# galvanika-board-1_0.net
KiCad netlist of a schematic drawn in EAGLE
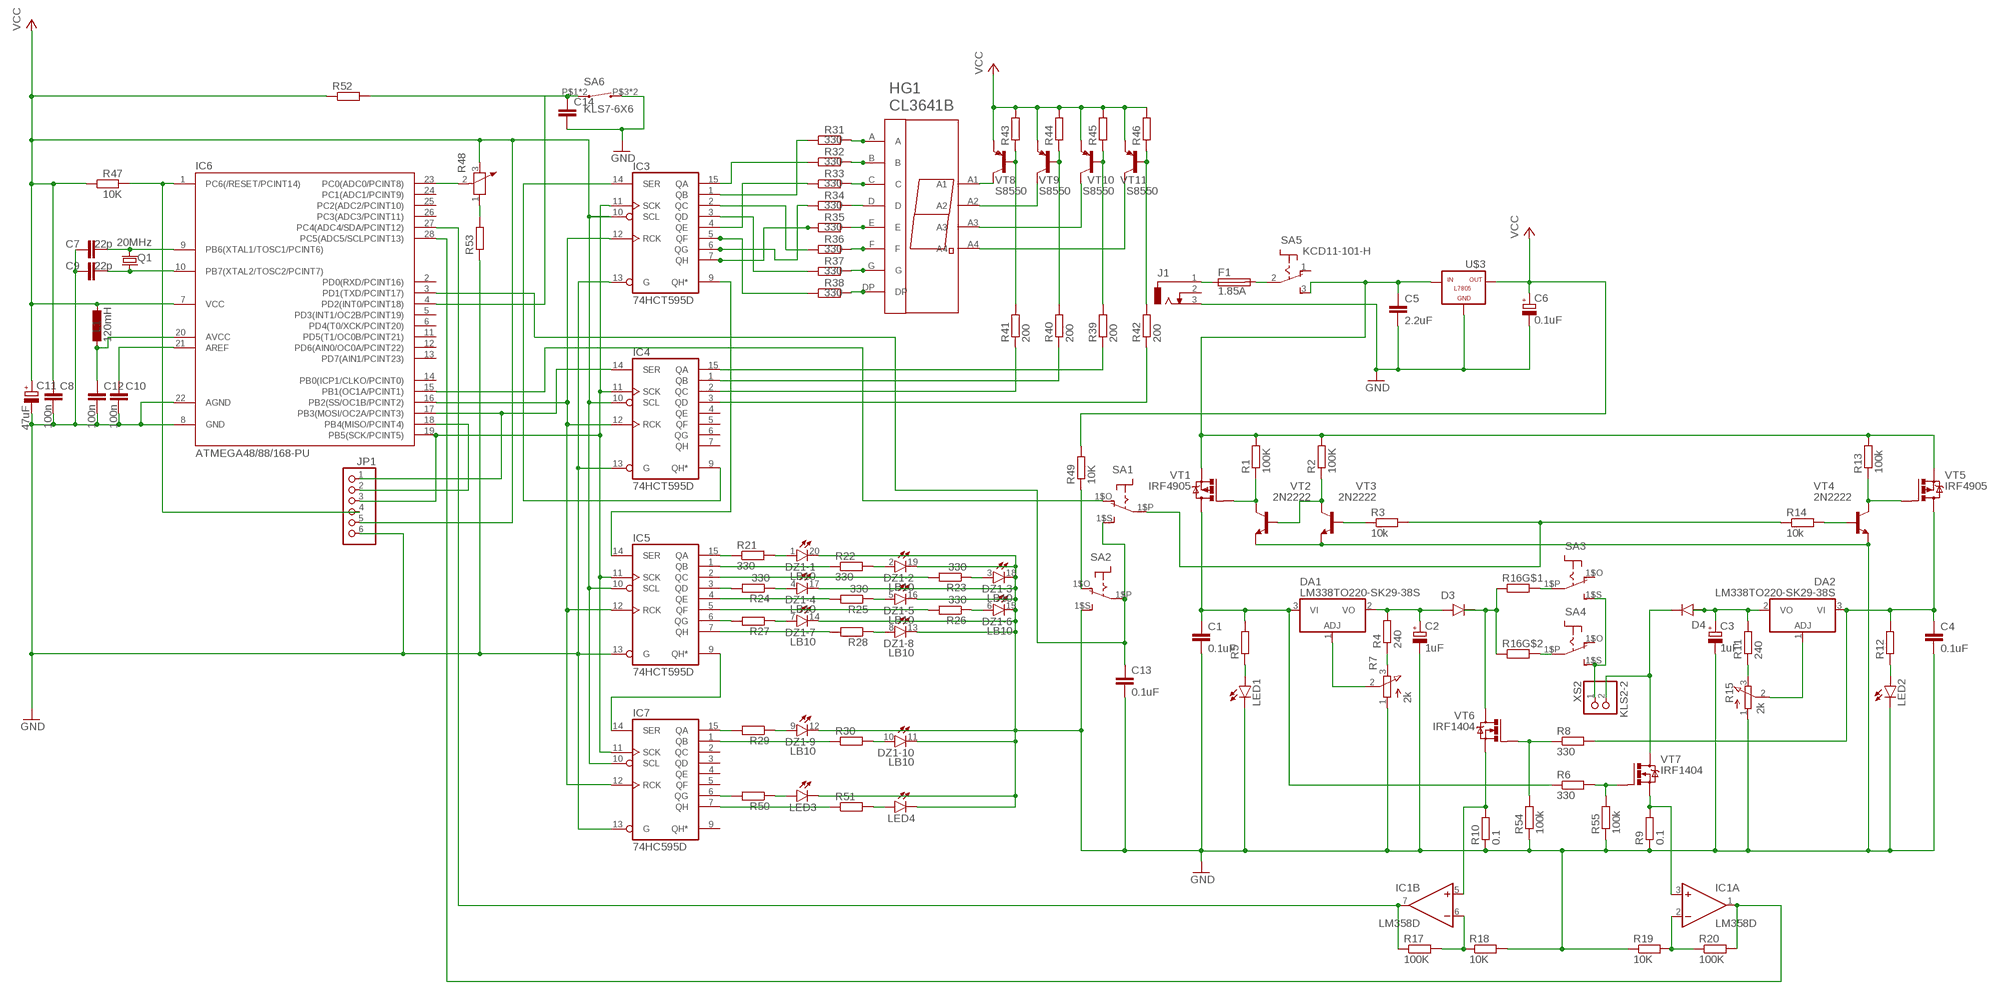
[diagram p0: schematic, sheet 1]

(export (version "E")
  (design (tool "Eeschema 10.0.6"))
  (components
    (comp (ref "C1")
      (value "0.1uF")
      (footprint "eagle-import:C1206")
      (libsource (lib "eagle-import") (part "rcl_334_C-EUC1206"))
    )
    (comp (ref "C2")
      (value "1uF")
      (footprint "eagle-import:E5-4")
      (libsource (lib "eagle-import") (part "CPOL-EUE5-4"))
    )
    (comp (ref "C3")
      (value "1uF")
      (footprint "eagle-import:E5-4")
      (libsource (lib "eagle-import") (part "CPOL-EUE5-4"))
    )
    (comp (ref "C4")
      (value "0.1uF")
      (footprint "eagle-import:C1206")
      (libsource (lib "eagle-import") (part "rcl_334_C-EUC1206"))
    )
    (comp (ref "C5")
      (value "2.2uF")
      (footprint "eagle-import:C025-025X050")
      (libsource (lib "eagle-import") (part "C-EU025-025X050"))
    )
    (comp (ref "C6")
      (value "0.1uF")
      (footprint "eagle-import:E2,5-5")
      (libsource (lib "eagle-import") (part "rcl_334_CPOL-EUE2.5-5"))
    )
    (comp (ref "C7")
      (value "22p")
      (footprint "eagle-import:C025-025X050")
      (libsource (lib "eagle-import") (part "rcl_334_C-EU025-025X050"))
    )
    (comp (ref "C8")
      (value "100n")
      (footprint "eagle-import:C025-025X050")
      (libsource (lib "eagle-import") (part "rcl_334_C-EU025-025X050"))
    )
    (comp (ref "C9")
      (value "22p")
      (footprint "eagle-import:C025-025X050")
      (libsource (lib "eagle-import") (part "rcl_334_C-EU025-025X050"))
    )
    (comp (ref "C10")
      (value "100n")
      (footprint "eagle-import:C025-025X050")
      (libsource (lib "eagle-import") (part "rcl_334_C-EU025-025X050"))
    )
    (comp (ref "C11")
      (value "47uF")
      (footprint "eagle-import:E2-4")
      (libsource (lib "eagle-import") (part "rcl_334_CPOL-EUE2-4"))
    )
    (comp (ref "C12")
      (value "100n")
      (footprint "eagle-import:C025-025X050")
      (libsource (lib "eagle-import") (part "rcl_334_C-EU025-025X050"))
    )
    (comp (ref "C13")
      (value "0.1uF")
      (footprint "eagle-import:C1206")
      (libsource (lib "eagle-import") (part "C-EUC1206"))
    )
    (comp (ref "C14")
      (value "C-EUC1206")
      (footprint "eagle-import:C1206")
      (libsource (lib "eagle-import") (part "C-EUC1206"))
    )
    (comp (ref "D3")
      (value "1N4001")
      (footprint "eagle-import:DO41-10")
      (libsource (lib "eagle-import") (part "1N4001"))
    )
    (comp (ref "D4")
      (value "1N4001")
      (footprint "eagle-import:DO41-10")
      (libsource (lib "eagle-import") (part "1N4001"))
    )
    (comp (ref "DA1")
      (value "LM338TO220-SK29-38S")
      (footprint "eagle-import:TO220-SK29-38S")
      (libsource (lib "eagle-import") (part "LM338TO220-SK29-38S"))
    )
    (comp (ref "DA2")
      (value "LM338TO220-SK29-38S")
      (footprint "eagle-import:TO220-SK29-38S")
      (libsource (lib "eagle-import") (part "LM338TO220-SK29-38S"))
    )
    (comp (ref "DZ1")
      (value "LB10")
      (footprint "eagle-import:LB10")
      (libsource (lib "eagle-import") (part "LB10"))
    )
    (comp (ref "F1")
      (value "1.85A")
      (footprint "eagle-import:MF-R")
      (libsource (lib "eagle-import") (part "MF-R"))
    )
    (comp (ref "HG1")
      (value "CL3641B")
      (footprint "eagle-import:CL3641B")
      (libsource (lib "eagle-import") (part "CL3641B"))
    )
    (comp (ref "IC1")
      (value "LM358D")
      (footprint "eagle-import:SO08")
      (libsource (lib "eagle-import") (part "LM358D"))
    )
    (comp (ref "IC3")
      (value "74HCT595D")
      (footprint "eagle-import:SO16")
      (libsource (lib "eagle-import") (part "74595DHCT"))
    )
    (comp (ref "IC4")
      (value "74HCT595D")
      (footprint "eagle-import:SO16")
      (libsource (lib "eagle-import") (part "74595DHCT"))
    )
    (comp (ref "IC5")
      (value "74HCT595D")
      (footprint "eagle-import:SO16")
      (libsource (lib "eagle-import") (part "74595DHCT"))
    )
    (comp (ref "IC6")
      (value "ATMEGA48/88/168-PU")
      (footprint "eagle-import:DIL28-3")
      (libsource (lib "eagle-import") (part "ATMEGA48/88/168-PU"))
    )
    (comp (ref "IC7")
      (value "74HC595D")
      (footprint "eagle-import:SO16")
      (libsource (lib "eagle-import") (part "74595DHC"))
    )
    (comp (ref "J1")
      (value "DCJ0303")
      (footprint "eagle-import:DCJ0303")
      (libsource (lib "eagle-import") (part "DCJ0303"))
    )
    (comp (ref "JP1")
      (value "PINHD-1X6")
      (footprint "eagle-import:1X06")
      (libsource (lib "eagle-import") (part "PINHD-1X6"))
    )
    (comp (ref "L1")
      (value "120mH")
      (footprint "eagle-import:0207_10")
      (libsource (lib "eagle-import") (part "L-EU0207/10"))
    )
    (comp (ref "LED1")
      (value "LED3MM")
      (footprint "eagle-import:LED3MM")
      (libsource (lib "eagle-import") (part "LED3MM"))
    )
    (comp (ref "LED2")
      (value "LED3MM")
      (footprint "eagle-import:LED3MM")
      (libsource (lib "eagle-import") (part "LED3MM"))
    )
    (comp (ref "LED3")
      (value "LED3MM")
      (footprint "eagle-import:LED3MM")
      (libsource (lib "eagle-import") (part "LED3MM"))
    )
    (comp (ref "LED4")
      (value "LED3MM")
      (footprint "eagle-import:LED3MM")
      (libsource (lib "eagle-import") (part "LED3MM"))
    )
    (comp (ref "Q1")
      (value "20MHz")
      (footprint "eagle-import:HC49_S")
      (libsource (lib "eagle-import") (part "CRYSTALHC49S"))
    )
    (comp (ref "R1")
      (value "100K")
      (footprint "eagle-import:0207_10")
      (libsource (lib "eagle-import") (part "rcl_334_R-EU_0207/10"))
    )
    (comp (ref "R2")
      (value "100K")
      (footprint "eagle-import:0207_10")
      (libsource (lib "eagle-import") (part "rcl_334_R-EU_0207/10"))
    )
    (comp (ref "R3")
      (value "10k")
      (footprint "eagle-import:0207_10")
      (libsource (lib "eagle-import") (part "rcl_334_R-EU_0207/10"))
    )
    (comp (ref "R4")
      (value "240")
      (footprint "eagle-import:0207_10")
      (libsource (lib "eagle-import") (part "R-EU_0207/10"))
    )
    (comp (ref "R5")
      (value "R-EU_0207/10")
      (footprint "eagle-import:0207_10")
      (libsource (lib "eagle-import") (part "R-EU_0207/10"))
    )
    (comp (ref "R6")
      (value "330")
      (footprint "eagle-import:0207_10")
      (libsource (lib "eagle-import") (part "rcl_334_R-EU_0207/10"))
    )
    (comp (ref "R7")
      (value "2k")
      (footprint "eagle-import:3RP_1610N")
      (libsource (lib "eagle-import") (part "3RP/1610N"))
    )
    (comp (ref "R8")
      (value "330")
      (footprint "eagle-import:0207_10")
      (libsource (lib "eagle-import") (part "rcl_334_R-EU_0207/10"))
    )
    (comp (ref "R9")
      (value "0.1")
      (footprint "eagle-import:0411_12")
      (libsource (lib "eagle-import") (part "rcl_334_R-EU_0411/12"))
    )
    (comp (ref "R10")
      (value "0.1")
      (footprint "eagle-import:0411_12")
      (libsource (lib "eagle-import") (part "rcl_334_R-EU_0411/12"))
    )
    (comp (ref "R11")
      (value "240")
      (footprint "eagle-import:0207_10")
      (libsource (lib "eagle-import") (part "rcl_334_R-EU_0207/10"))
    )
    (comp (ref "R12")
      (value "R-EU_0207/10")
      (footprint "eagle-import:0207_10")
      (libsource (lib "eagle-import") (part "R-EU_0207/10"))
    )
    (comp (ref "R13")
      (value "100k")
      (footprint "eagle-import:0207_10")
      (libsource (lib "eagle-import") (part "rcl_334_R-EU_0207/10"))
    )
    (comp (ref "R14")
      (value "10k")
      (footprint "eagle-import:0207_10")
      (libsource (lib "eagle-import") (part "rcl_334_R-EU_0207/10"))
    )
    (comp (ref "R15")
      (value "2k")
      (footprint "eagle-import:3RP_1610N")
      (libsource (lib "eagle-import") (part "3RP/1610N"))
    )
    (comp (ref "R16")
      (value "SQP-5W-2")
      (footprint "eagle-import:SQP-5W-2")
      (libsource (lib "eagle-import") (part "SQP-5W-2"))
    )
    (comp (ref "R17")
      (value "100K")
      (footprint "eagle-import:R1206")
      (libsource (lib "eagle-import") (part "rcl_334_R-EU_R1206"))
    )
    (comp (ref "R18")
      (value "10K")
      (footprint "eagle-import:R1206")
      (libsource (lib "eagle-import") (part "rcl_334_R-EU_R1206"))
    )
    (comp (ref "R19")
      (value "10K")
      (footprint "eagle-import:R1206")
      (libsource (lib "eagle-import") (part "rcl_334_R-EU_R1206"))
    )
    (comp (ref "R20")
      (value "100K")
      (footprint "eagle-import:R1206")
      (libsource (lib "eagle-import") (part "rcl_334_R-EU_R1206"))
    )
    (comp (ref "R21")
      (value "330")
      (footprint "eagle-import:R1206")
      (libsource (lib "eagle-import") (part "rcl_334_R-EU_R1206"))
    )
    (comp (ref "R22")
      (value "330")
      (footprint "eagle-import:R1206")
      (libsource (lib "eagle-import") (part "rcl_334_R-EU_R1206"))
    )
    (comp (ref "R23")
      (value "330")
      (footprint "eagle-import:R1206")
      (libsource (lib "eagle-import") (part "rcl_334_R-EU_R1206"))
    )
    (comp (ref "R24")
      (value "330")
      (footprint "eagle-import:R1206")
      (libsource (lib "eagle-import") (part "rcl_334_R-EU_R1206"))
    )
    (comp (ref "R25")
      (value "330")
      (footprint "eagle-import:R1206")
      (libsource (lib "eagle-import") (part "rcl_334_R-EU_R1206"))
    )
    (comp (ref "R26")
      (value "330")
      (footprint "eagle-import:R1206")
      (libsource (lib "eagle-import") (part "rcl_334_R-EU_R1206"))
    )
    (comp (ref "R27")
      (value "R-EU_R1206")
      (footprint "eagle-import:R1206")
      (libsource (lib "eagle-import") (part "rcl_334_R-EU_R1206"))
    )
    (comp (ref "R28")
      (value "R-EU_R1206")
      (footprint "eagle-import:R1206")
      (libsource (lib "eagle-import") (part "rcl_334_R-EU_R1206"))
    )
    (comp (ref "R29")
      (value "R-EU_R1206")
      (footprint "eagle-import:R1206")
      (libsource (lib "eagle-import") (part "rcl_334_R-EU_R1206"))
    )
    (comp (ref "R30")
      (value "R-EU_R1206")
      (footprint "eagle-import:R1206")
      (libsource (lib "eagle-import") (part "rcl_334_R-EU_R1206"))
    )
    (comp (ref "R31")
      (value "330")
      (footprint "eagle-import:R1206")
      (libsource (lib "eagle-import") (part "rcl_334_R-EU_R1206"))
    )
    (comp (ref "R32")
      (value "330")
      (footprint "eagle-import:R1206")
      (libsource (lib "eagle-import") (part "rcl_334_R-EU_R1206"))
    )
    (comp (ref "R33")
      (value "330")
      (footprint "eagle-import:R1206")
      (libsource (lib "eagle-import") (part "rcl_334_R-EU_R1206"))
    )
    (comp (ref "R34")
      (value "330")
      (footprint "eagle-import:R1206")
      (libsource (lib "eagle-import") (part "rcl_334_R-EU_R1206"))
    )
    (comp (ref "R35")
      (value "330")
      (footprint "eagle-import:R1206")
      (libsource (lib "eagle-import") (part "rcl_334_R-EU_R1206"))
    )
    (comp (ref "R36")
      (value "330")
      (footprint "eagle-import:R1206")
      (libsource (lib "eagle-import") (part "rcl_334_R-EU_R1206"))
    )
    (comp (ref "R37")
      (value "330")
      (footprint "eagle-import:R1206")
      (libsource (lib "eagle-import") (part "rcl_334_R-EU_R1206"))
    )
    (comp (ref "R38")
      (value "330")
      (footprint "eagle-import:R1206")
      (libsource (lib "eagle-import") (part "rcl_334_R-EU_R1206"))
    )
    (comp (ref "R39")
      (value "200")
      (footprint "eagle-import:R1206")
      (libsource (lib "eagle-import") (part "rcl_334_R-EU_R1206"))
    )
    (comp (ref "R40")
      (value "200")
      (footprint "eagle-import:R1206")
      (libsource (lib "eagle-import") (part "rcl_334_R-EU_R1206"))
    )
    (comp (ref "R41")
      (value "200")
      (footprint "eagle-import:R1206")
      (libsource (lib "eagle-import") (part "rcl_334_R-EU_R1206"))
    )
    (comp (ref "R42")
      (value "200")
      (footprint "eagle-import:R1206")
      (libsource (lib "eagle-import") (part "rcl_334_R-EU_R1206"))
    )
    (comp (ref "R43")
      (value "R-EU_R1206")
      (footprint "eagle-import:R1206")
      (libsource (lib "eagle-import") (part "R-EU_R1206"))
    )
    (comp (ref "R44")
      (value "R-EU_R1206")
      (footprint "eagle-import:R1206")
      (libsource (lib "eagle-import") (part "R-EU_R1206"))
    )
    (comp (ref "R45")
      (value "R-EU_R1206")
      (footprint "eagle-import:R1206")
      (libsource (lib "eagle-import") (part "R-EU_R1206"))
    )
    (comp (ref "R46")
      (value "R-EU_R1206")
      (footprint "eagle-import:R1206")
      (libsource (lib "eagle-import") (part "R-EU_R1206"))
    )
    (comp (ref "R47")
      (value "10K")
      (footprint "eagle-import:0207_10")
      (libsource (lib "eagle-import") (part "R-EU_0207/10"))
    )
    (comp (ref "R48")
      (value "R0904N")
      (footprint "eagle-import:R0904N")
      (libsource (lib "eagle-import") (part "R0904N"))
    )
    (comp (ref "R49")
      (value "10K")
      (footprint "eagle-import:0207_10")
      (libsource (lib "eagle-import") (part "R-EU_0207/10"))
    )
    (comp (ref "R50")
      (value "R-EU_R1206")
      (footprint "eagle-import:R1206")
      (libsource (lib "eagle-import") (part "rcl_334_R-EU_R1206"))
    )
    (comp (ref "R51")
      (value "R-EU_R1206")
      (footprint "eagle-import:R1206")
      (libsource (lib "eagle-import") (part "rcl_334_R-EU_R1206"))
    )
    (comp (ref "R52")
      (value "R-EU_R1206")
      (footprint "eagle-import:R1206")
      (libsource (lib "eagle-import") (part "R-EU_R1206"))
    )
    (comp (ref "R53")
      (value "R-EU_R1206")
      (footprint "eagle-import:R1206")
      (libsource (lib "eagle-import") (part "R-EU_R1206"))
    )
    (comp (ref "R54")
      (value "100k")
      (footprint "eagle-import:R1206")
      (libsource (lib "eagle-import") (part "R-EU_R1206"))
    )
    (comp (ref "R55")
      (value "100k")
      (footprint "eagle-import:R1206")
      (libsource (lib "eagle-import") (part "R-EU_R1206"))
    )
    (comp (ref "SA1")
      (value "SS12D00DIP")
      (footprint "eagle-import:SS12D00")
      (libsource (lib "eagle-import") (part "SS12D00DIP"))
    )
    (comp (ref "SA2")
      (value "SS12D00DIP")
      (footprint "eagle-import:SS12D00")
      (libsource (lib "eagle-import") (part "SS12D00DIP"))
    )
    (comp (ref "SA3")
      (value "SS12D00DIP")
      (footprint "eagle-import:SS12D00")
      (libsource (lib "eagle-import") (part "SS12D00DIP"))
    )
    (comp (ref "SA4")
      (value "SS12D00DIP")
      (footprint "eagle-import:SS12D00")
      (libsource (lib "eagle-import") (part "SS12D00DIP"))
    )
    (comp (ref "SA5")
      (value "KCD11-101-H")
      (footprint "eagle-import:KCD11-101-H")
      (libsource (lib "eagle-import") (part "KCD11-101-H"))
    )
    (comp (ref "SA6")
      (value "KLS7-6X6")
      (footprint "eagle-import:KLS7-6X6")
      (libsource (lib "eagle-import") (part "KLS7-6X6"))
    )
    (comp (ref "U$3")
      (value "L7805")
      (footprint "eagle-import:TO220-SK29-38S")
      (libsource (lib "eagle-import") (part "L7805"))
    )
    (comp (ref "VT1")
      (value "IRF4905")
      (footprint "eagle-import:TO220-V")
      (libsource (lib "eagle-import") (part "IRF4905"))
    )
    (comp (ref "VT2")
      (value "2N2222")
      (footprint "eagle-import:TO92")
      (libsource (lib "eagle-import") (part "2N2222"))
    )
    (comp (ref "VT3")
      (value "2N2222")
      (footprint "eagle-import:TO92")
      (libsource (lib "eagle-import") (part "2N2222"))
    )
    (comp (ref "VT4")
      (value "2N2222")
      (footprint "eagle-import:TO92")
      (libsource (lib "eagle-import") (part "2N2222"))
    )
    (comp (ref "VT5")
      (value "IRF4905")
      (footprint "eagle-import:TO220-V")
      (libsource (lib "eagle-import") (part "IRF4905"))
    )
    (comp (ref "VT6")
      (value "IRF1404")
      (footprint "eagle-import:TO220-V")
      (libsource (lib "eagle-import") (part "IRF1404"))
    )
    (comp (ref "VT7")
      (value "IRF1404")
      (footprint "eagle-import:TO220-V")
      (libsource (lib "eagle-import") (part "IRF1404"))
    )
    (comp (ref "VT8")
      (value "S8550")
      (footprint "eagle-import:TO92")
      (libsource (lib "eagle-import") (part "S8550"))
    )
    (comp (ref "VT9")
      (value "S8550")
      (footprint "eagle-import:TO92")
      (libsource (lib "eagle-import") (part "S8550"))
    )
    (comp (ref "VT10")
      (value "S8550")
      (footprint "eagle-import:TO92")
      (libsource (lib "eagle-import") (part "S8550"))
    )
    (comp (ref "VT11")
      (value "S8550")
      (footprint "eagle-import:TO92")
      (libsource (lib "eagle-import") (part "S8550"))
    )
    (comp (ref "XS2")
      (value "KLS2-2")
      (footprint "eagle-import:KLS2-2")
      (libsource (lib "eagle-import") (part "KLS2-2"))
    )
  )
  (nets
    (net (code "1") (name "GND") (class "Default")
      (node (ref "C1") (pin "2") (pinfunction "2_2") (pintype "passive"))
      (node (ref "C10") (pin "2") (pinfunction "2_2") (pintype "passive"))
      (node (ref "C11") (pin "-") (pinfunction "-_-") (pintype "passive"))
      (node (ref "C12") (pin "2") (pinfunction "2_2") (pintype "passive"))
      (node (ref "C13") (pin "2") (pinfunction "2_2") (pintype "passive"))
      (node (ref "C14") (pin "2") (pinfunction "2_2") (pintype "passive"))
      (node (ref "C2") (pin "-") (pinfunction "-_-") (pintype "passive"))
      (node (ref "C3") (pin "-") (pinfunction "-_-") (pintype "passive"))
      (node (ref "C4") (pin "2") (pinfunction "2_2") (pintype "passive"))
      (node (ref "C5") (pin "2") (pinfunction "2_2") (pintype "passive"))
      (node (ref "C6") (pin "-") (pinfunction "-_-") (pintype "passive"))
      (node (ref "C7") (pin "1") (pinfunction "1_1") (pintype "passive"))
      (node (ref "C8") (pin "2") (pinfunction "2_2") (pintype "passive"))
      (node (ref "C9") (pin "1") (pinfunction "1_1") (pintype "passive"))
      (node (ref "DZ1") (pin "11") (pinfunction "C_11") (pintype "passive"))
      (node (ref "DZ1") (pin "12") (pinfunction "C_12") (pintype "passive"))
      (node (ref "DZ1") (pin "13") (pinfunction "C_13") (pintype "passive"))
      (node (ref "DZ1") (pin "14") (pinfunction "C_14") (pintype "passive"))
      (node (ref "DZ1") (pin "15") (pinfunction "C_15") (pintype "passive"))
      (node (ref "DZ1") (pin "16") (pinfunction "C_16") (pintype "passive"))
      (node (ref "DZ1") (pin "17") (pinfunction "C_17") (pintype "passive"))
      (node (ref "DZ1") (pin "18") (pinfunction "C_18") (pintype "passive"))
      (node (ref "DZ1") (pin "19") (pinfunction "C_19") (pintype "passive"))
      (node (ref "DZ1") (pin "20") (pinfunction "C_20") (pintype "passive"))
      (node (ref "IC3") (pin "13") (pinfunction "G_13") (pintype "input"))
      (node (ref "IC4") (pin "13") (pinfunction "G_13") (pintype "input"))
      (node (ref "IC5") (pin "13") (pinfunction "G_13") (pintype "input"))
      (node (ref "IC6") (pin "22") (pinfunction "AGND_22") (pintype "power_in"))
      (node (ref "IC6") (pin "8") (pinfunction "GND_8") (pintype "power_in"))
      (node (ref "IC7") (pin "13") (pinfunction "G_13") (pintype "input"))
      (node (ref "J1") (pin "3") (pinfunction "3_3") (pintype "passive"))
      (node (ref "JP1") (pin "6") (pinfunction "6_6") (pintype "passive"))
      (node (ref "LED1") (pin "K") (pinfunction "C_K") (pintype "passive"))
      (node (ref "LED2") (pin "K") (pinfunction "C_K") (pintype "passive"))
      (node (ref "LED3") (pin "K") (pinfunction "C_K") (pintype "passive"))
      (node (ref "LED4") (pin "K") (pinfunction "C_K") (pintype "passive"))
      (node (ref "R10") (pin "1") (pinfunction "1_1") (pintype "passive"))
      (node (ref "R15") (pin "1") (pinfunction "A_1") (pintype "passive"))
      (node (ref "R18") (pin "2") (pinfunction "2_2") (pintype "passive"))
      (node (ref "R19") (pin "1") (pinfunction "1_1") (pintype "passive"))
      (node (ref "R53") (pin "1") (pinfunction "1_1") (pintype "passive"))
      (node (ref "R54") (pin "1") (pinfunction "1_1") (pintype "passive"))
      (node (ref "R55") (pin "1") (pinfunction "1_1") (pintype "passive"))
      (node (ref "R7") (pin "1") (pinfunction "A_1") (pintype "passive"))
      (node (ref "R9") (pin "1") (pinfunction "1_1") (pintype "passive"))
      (node (ref "SA2") (pin "1$S") (pinfunction "S_1$S") (pintype "passive"))
      (node (ref "SA6") (pin "P$3") (pinfunction "2_P$3") (pintype "passive"))
      (node (ref "SA6") (pin "P$4") (pinfunction "2_P$4") (pintype "passive"))
      (node (ref "U$3") (pin "2") (pinfunction "GND_2") (pintype "input"))
      (node (ref "VT2") (pin "3") (pinfunction "E_3") (pintype "passive"))
      (node (ref "VT3") (pin "3") (pinfunction "E_3") (pintype "passive"))
      (node (ref "VT4") (pin "3") (pinfunction "E_3") (pintype "passive"))
    )
    (net (code "2") (name "Net-(D3-ANODE)") (class "Default")
      (node (ref "C2") (pin "+") (pinfunction "+_+") (pintype "passive"))
      (node (ref "D3") (pin "A") (pinfunction "ANODE_A") (pintype "passive"))
      (node (ref "DA1") (pin "2") (pinfunction "VO_2") (pintype "passive"))
      (node (ref "R4") (pin "2") (pinfunction "2_2") (pintype "passive"))
    )
    (net (code "3") (name "Net-(D3-CATHODE)") (class "Default")
      (node (ref "D3") (pin "C") (pinfunction "CATHODE_C") (pintype "passive"))
      (node (ref "R16") (pin "1") (pinfunction "1_1") (pintype "passive"))
      (node (ref "R16") (pin "3") (pinfunction "1_3") (pintype "passive"))
      (node (ref "VT6") (pin "D") (pinfunction "D_D") (pintype "passive"))
    )
    (net (code "4") (name "Net-(D4-ANODE)") (class "Default")
      (node (ref "C3") (pin "+") (pinfunction "+_+") (pintype "passive"))
      (node (ref "D4") (pin "A") (pinfunction "ANODE_A") (pintype "passive"))
      (node (ref "DA2") (pin "2") (pinfunction "VO_2") (pintype "passive"))
      (node (ref "R11") (pin "2") (pinfunction "2_2") (pintype "passive"))
    )
    (net (code "5") (name "Net-(D4-CATHODE)") (class "Default")
      (node (ref "D4") (pin "C") (pinfunction "CATHODE_C") (pintype "passive"))
      (node (ref "VT7") (pin "D") (pinfunction "D_D") (pintype "passive"))
      (node (ref "XS2") (pin "2") (pinfunction "2_2") (pintype "passive"))
    )
    (net (code "6") (name "Net-(DA1-ADJ)") (class "Default")
      (node (ref "DA1") (pin "1") (pinfunction "ADJ_1") (pintype "passive"))
      (node (ref "R7") (pin "2") (pinfunction "S_2") (pintype "passive"))
    )
    (net (code "7") (name "Net-(DA1-VI)") (class "Default")
      (node (ref "C1") (pin "1") (pinfunction "1_1") (pintype "passive"))
      (node (ref "DA1") (pin "3") (pinfunction "VI_3") (pintype "input"))
      (node (ref "R5") (pin "2") (pinfunction "2_2") (pintype "passive"))
      (node (ref "R6") (pin "1") (pinfunction "1_1") (pintype "passive"))
      (node (ref "VT1") (pin "D") (pinfunction "D_D") (pintype "passive"))
    )
    (net (code "8") (name "Net-(DA2-ADJ)") (class "Default")
      (node (ref "DA2") (pin "1") (pinfunction "ADJ_1") (pintype "passive"))
      (node (ref "R15") (pin "2") (pinfunction "S_2") (pintype "passive"))
    )
    (net (code "9") (name "Net-(DA2-VI)") (class "Default")
      (node (ref "C4") (pin "1") (pinfunction "1_1") (pintype "passive"))
      (node (ref "DA2") (pin "3") (pinfunction "VI_3") (pintype "input"))
      (node (ref "R12") (pin "2") (pinfunction "2_2") (pintype "passive"))
      (node (ref "R8") (pin "2") (pinfunction "2_2") (pintype "passive"))
      (node (ref "VT5") (pin "D") (pinfunction "D_D") (pintype "passive"))
    )
    (net (code "10") (name "Net-(DZ1A-A)") (class "Default")
      (node (ref "DZ1") (pin "1") (pinfunction "A_1") (pintype "passive"))
      (node (ref "R21") (pin "2") (pinfunction "2_2") (pintype "passive"))
    )
    (net (code "11") (name "Net-(DZ1B-A)") (class "Default")
      (node (ref "DZ1") (pin "10") (pinfunction "A_10") (pintype "passive"))
      (node (ref "R30") (pin "2") (pinfunction "2_2") (pintype "passive"))
    )
    (net (code "12") (name "Net-(DZ1C-A)") (class "Default")
      (node (ref "DZ1") (pin "2") (pinfunction "A_2") (pintype "passive"))
      (node (ref "R22") (pin "2") (pinfunction "2_2") (pintype "passive"))
    )
    (net (code "13") (name "Net-(DZ1D-A)") (class "Default")
      (node (ref "DZ1") (pin "3") (pinfunction "A_3") (pintype "passive"))
      (node (ref "R23") (pin "1") (pinfunction "1_1") (pintype "passive"))
    )
    (net (code "14") (name "Net-(DZ1E-A)") (class "Default")
      (node (ref "DZ1") (pin "4") (pinfunction "A_4") (pintype "passive"))
      (node (ref "R24") (pin "1") (pinfunction "1_1") (pintype "passive"))
    )
    (net (code "15") (name "Net-(DZ1F-A)") (class "Default")
      (node (ref "DZ1") (pin "5") (pinfunction "A_5") (pintype "passive"))
      (node (ref "R25") (pin "1") (pinfunction "1_1") (pintype "passive"))
    )
    (net (code "16") (name "Net-(DZ1G-A)") (class "Default")
      (node (ref "DZ1") (pin "6") (pinfunction "A_6") (pintype "passive"))
      (node (ref "R26") (pin "1") (pinfunction "1_1") (pintype "passive"))
    )
    (net (code "17") (name "Net-(DZ1H-A)") (class "Default")
      (node (ref "DZ1") (pin "7") (pinfunction "A_7") (pintype "passive"))
      (node (ref "R27") (pin "1") (pinfunction "1_1") (pintype "passive"))
    )
    (net (code "18") (name "Net-(DZ1I-A)") (class "Default")
      (node (ref "DZ1") (pin "8") (pinfunction "A_8") (pintype "passive"))
      (node (ref "R28") (pin "1") (pinfunction "1_1") (pintype "passive"))
    )
    (net (code "19") (name "Net-(DZ1J-A)") (class "Default")
      (node (ref "DZ1") (pin "9") (pinfunction "A_9") (pintype "passive"))
      (node (ref "R29") (pin "1") (pinfunction "1_1") (pintype "passive"))
    )
    (net (code "20") (name "Net-(F1-Pad1)") (class "Default")
      (node (ref "F1") (pin "1") (pinfunction "1_1") (pintype "passive"))
      (node (ref "J1") (pin "1") (pinfunction "1_1") (pintype "passive"))
    )
    (net (code "21") (name "Net-(HG1-PadA)") (class "Default")
      (node (ref "HG1") (pin "A") (pinfunction "A_A") (pintype "output"))
      (node (ref "R31") (pin "2") (pinfunction "2_2") (pintype "passive"))
    )
    (net (code "22") (name "Net-(HG1-PadB)") (class "Default")
      (node (ref "HG1") (pin "B") (pinfunction "B_B") (pintype "output"))
      (node (ref "R32") (pin "2") (pinfunction "2_2") (pintype "passive"))
    )
    (net (code "23") (name "Net-(HG1-PadC)") (class "Default")
      (node (ref "HG1") (pin "C") (pinfunction "C_C") (pintype "output"))
      (node (ref "R33") (pin "2") (pinfunction "2_2") (pintype "passive"))
    )
    (net (code "24") (name "Net-(HG1-PadD)") (class "Default")
      (node (ref "HG1") (pin "D") (pinfunction "D_D") (pintype "output"))
      (node (ref "R34") (pin "2") (pinfunction "2_2") (pintype "passive"))
    )
    (net (code "25") (name "Net-(HG1-PadDP)") (class "Default")
      (node (ref "HG1") (pin "DP") (pinfunction "DP_DP") (pintype "output"))
      (node (ref "R38") (pin "2") (pinfunction "2_2") (pintype "passive"))
    )
    (net (code "26") (name "Net-(HG1-PadE)") (class "Default")
      (node (ref "HG1") (pin "E") (pinfunction "E_E") (pintype "output"))
      (node (ref "R35") (pin "2") (pinfunction "2_2") (pintype "passive"))
    )
    (net (code "27") (name "Net-(HG1-PadF)") (class "Default")
      (node (ref "HG1") (pin "F") (pinfunction "F_F") (pintype "output"))
      (node (ref "R36") (pin "2") (pinfunction "2_2") (pintype "passive"))
    )
    (net (code "28") (name "Net-(HG1-PadG)") (class "Default")
      (node (ref "HG1") (pin "G") (pinfunction "G_G") (pintype "output"))
      (node (ref "R37") (pin "2") (pinfunction "2_2") (pintype "passive"))
    )
    (net (code "29") (name "Net-(IC1A-+IN)") (class "Default")
      (node (ref "IC1") (pin "3") (pinfunction "+IN_3") (pintype "input"))
      (node (ref "R9") (pin "2") (pinfunction "2_2") (pintype "passive"))
      (node (ref "VT7") (pin "S") (pinfunction "S_S") (pintype "passive"))
    )
    (net (code "30") (name "Net-(IC1A--IN)") (class "Default")
      (node (ref "IC1") (pin "2") (pinfunction "-IN_2") (pintype "input"))
      (node (ref "R19") (pin "2") (pinfunction "2_2") (pintype "passive"))
      (node (ref "R20") (pin "1") (pinfunction "1_1") (pintype "passive"))
    )
    (net (code "31") (name "Net-(IC1A-OUT)") (class "Default")
      (node (ref "IC1") (pin "1") (pinfunction "OUT_1") (pintype "output"))
      (node (ref "IC6") (pin "28") (pinfunction "PC5(ADC5/SCLPCINT13)_28") (pintype "bidirectional"))
      (node (ref "R20") (pin "2") (pinfunction "2_2") (pintype "passive"))
    )
    (net (code "32") (name "Net-(IC1B-+IN)") (class "Default")
      (node (ref "IC1") (pin "5") (pinfunction "+IN_5") (pintype "input"))
      (node (ref "R10") (pin "2") (pinfunction "2_2") (pintype "passive"))
      (node (ref "VT6") (pin "S") (pinfunction "S_S") (pintype "passive"))
    )
    (net (code "33") (name "Net-(IC1B--IN)") (class "Default")
      (node (ref "IC1") (pin "6") (pinfunction "-IN_6") (pintype "input"))
      (node (ref "R17") (pin "2") (pinfunction "2_2") (pintype "passive"))
      (node (ref "R18") (pin "1") (pinfunction "1_1") (pintype "passive"))
    )
    (net (code "34") (name "Net-(IC1B-OUT)") (class "Default")
      (node (ref "IC1") (pin "7") (pinfunction "OUT_7") (pintype "output"))
      (node (ref "IC6") (pin "27") (pinfunction "PC4(ADC4/SDA/PCINT12)_27") (pintype "bidirectional"))
      (node (ref "R17") (pin "1") (pinfunction "1_1") (pintype "passive"))
    )
    (net (code "35") (name "Net-(IC3A-QA)") (class "Default")
      (node (ref "IC3") (pin "15") (pinfunction "QA_15") (pintype "tri_state"))
      (node (ref "R32") (pin "1") (pinfunction "1_1") (pintype "passive"))
    )
    (net (code "36") (name "Net-(IC3A-QB)") (class "Default")
      (node (ref "IC3") (pin "1") (pinfunction "QB_1") (pintype "tri_state"))
      (node (ref "R31") (pin "1") (pinfunction "1_1") (pintype "passive"))
    )
    (net (code "37") (name "Net-(IC3A-QC)") (class "Default")
      (node (ref "IC3") (pin "2") (pinfunction "QC_2") (pintype "tri_state"))
      (node (ref "R36") (pin "1") (pinfunction "1_1") (pintype "passive"))
    )
    (net (code "38") (name "Net-(IC3A-QD)") (class "Default")
      (node (ref "IC3") (pin "3") (pinfunction "QD_3") (pintype "tri_state"))
      (node (ref "R37") (pin "1") (pinfunction "1_1") (pintype "passive"))
    )
    (net (code "39") (name "Net-(IC3A-QE)") (class "Default")
      (node (ref "IC3") (pin "4") (pinfunction "QE_4") (pintype "tri_state"))
      (node (ref "R33") (pin "1") (pinfunction "1_1") (pintype "passive"))
    )
    (net (code "40") (name "Net-(IC3A-QF)") (class "Default")
      (node (ref "IC3") (pin "5") (pinfunction "QF_5") (pintype "tri_state"))
      (node (ref "R38") (pin "1") (pinfunction "1_1") (pintype "passive"))
    )
    (net (code "41") (name "Net-(IC3A-QG)") (class "Default")
      (node (ref "IC3") (pin "6") (pinfunction "QG_6") (pintype "tri_state"))
      (node (ref "R34") (pin "1") (pinfunction "1_1") (pintype "passive"))
    )
    (net (code "42") (name "Net-(IC3A-QH)") (class "Default")
      (node (ref "IC3") (pin "7") (pinfunction "QH_7") (pintype "tri_state"))
      (node (ref "R35") (pin "1") (pinfunction "1_1") (pintype "passive"))
    )
    (net (code "43") (name "Net-(IC3A-QH*)") (class "Default")
      (node (ref "IC3") (pin "9") (pinfunction "QH*_9") (pintype "tri_state"))
      (node (ref "IC5") (pin "14") (pinfunction "SER_14") (pintype "input"))
    )
    (net (code "44") (name "Net-(IC3A-RCK)") (class "Default")
      (node (ref "IC3") (pin "12") (pinfunction "RCK_12") (pintype "input"))
      (node (ref "IC4") (pin "12") (pinfunction "RCK_12") (pintype "input"))
      (node (ref "IC5") (pin "12") (pinfunction "RCK_12") (pintype "input"))
      (node (ref "IC6") (pin "16") (pinfunction "PB2(SS/OC1B/PCINT2)_16") (pintype "bidirectional"))
      (node (ref "IC7") (pin "12") (pinfunction "RCK_12") (pintype "input"))
    )
    (net (code "45") (name "Net-(IC3A-SCK)") (class "Default")
      (node (ref "IC3") (pin "11") (pinfunction "SCK_11") (pintype "input"))
      (node (ref "IC4") (pin "11") (pinfunction "SCK_11") (pintype "input"))
      (node (ref "IC5") (pin "11") (pinfunction "SCK_11") (pintype "input"))
      (node (ref "IC6") (pin "19") (pinfunction "PB5(SCK/PCINT5)_19") (pintype "bidirectional"))
      (node (ref "IC7") (pin "11") (pinfunction "SCK_11") (pintype "input"))
      (node (ref "JP1") (pin "3") (pinfunction "3_3") (pintype "passive"))
    )
    (net (code "46") (name "Net-(IC3A-SER)") (class "Default")
      (node (ref "IC3") (pin "14") (pinfunction "SER_14") (pintype "input"))
      (node (ref "IC4") (pin "9") (pinfunction "QH*_9") (pintype "tri_state"))
    )
    (net (code "47") (name "Net-(IC4A-QA)") (class "Default")
      (node (ref "IC4") (pin "15") (pinfunction "QA_15") (pintype "tri_state"))
      (node (ref "R39") (pin "1") (pinfunction "1_1") (pintype "passive"))
    )
    (net (code "48") (name "Net-(IC4A-QB)") (class "Default")
      (node (ref "IC4") (pin "1") (pinfunction "QB_1") (pintype "tri_state"))
      (node (ref "R40") (pin "1") (pinfunction "1_1") (pintype "passive"))
    )
    (net (code "49") (name "Net-(IC4A-QC)") (class "Default")
      (node (ref "IC4") (pin "2") (pinfunction "QC_2") (pintype "tri_state"))
      (node (ref "R41") (pin "1") (pinfunction "1_1") (pintype "passive"))
    )
    (net (code "50") (name "Net-(IC4A-QD)") (class "Default")
      (node (ref "IC4") (pin "3") (pinfunction "QD_3") (pintype "tri_state"))
      (node (ref "R42") (pin "1") (pinfunction "1_1") (pintype "passive"))
    )
    (net (code "51") (name "Net-(IC4A-SER)") (class "Default")
      (node (ref "IC4") (pin "14") (pinfunction "SER_14") (pintype "input"))
      (node (ref "IC6") (pin "17") (pinfunction "PB3(MOSI/OC2A/PCINT3)_17") (pintype "bidirectional"))
      (node (ref "JP1") (pin "1") (pinfunction "1_1") (pintype "passive"))
    )
    (net (code "52") (name "Net-(IC5A-QA)") (class "Default")
      (node (ref "IC5") (pin "15") (pinfunction "QA_15") (pintype "tri_state"))
      (node (ref "R21") (pin "1") (pinfunction "1_1") (pintype "passive"))
    )
    (net (code "53") (name "Net-(IC5A-QB)") (class "Default")
      (node (ref "IC5") (pin "1") (pinfunction "QB_1") (pintype "tri_state"))
      (node (ref "R22") (pin "1") (pinfunction "1_1") (pintype "passive"))
    )
    (net (code "54") (name "Net-(IC5A-QC)") (class "Default")
      (node (ref "IC5") (pin "2") (pinfunction "QC_2") (pintype "tri_state"))
      (node (ref "R23") (pin "2") (pinfunction "2_2") (pintype "passive"))
    )
    (net (code "55") (name "Net-(IC5A-QD)") (class "Default")
      (node (ref "IC5") (pin "3") (pinfunction "QD_3") (pintype "tri_state"))
      (node (ref "R24") (pin "2") (pinfunction "2_2") (pintype "passive"))
    )
    (net (code "56") (name "Net-(IC5A-QE)") (class "Default")
      (node (ref "IC5") (pin "4") (pinfunction "QE_4") (pintype "tri_state"))
      (node (ref "R25") (pin "2") (pinfunction "2_2") (pintype "passive"))
    )
    (net (code "57") (name "Net-(IC5A-QF)") (class "Default")
      (node (ref "IC5") (pin "5") (pinfunction "QF_5") (pintype "tri_state"))
      (node (ref "R26") (pin "2") (pinfunction "2_2") (pintype "passive"))
    )
    (net (code "58") (name "Net-(IC5A-QG)") (class "Default")
      (node (ref "IC5") (pin "6") (pinfunction "QG_6") (pintype "tri_state"))
      (node (ref "R27") (pin "2") (pinfunction "2_2") (pintype "passive"))
    )
    (net (code "59") (name "Net-(IC5A-QH)") (class "Default")
      (node (ref "IC5") (pin "7") (pinfunction "QH_7") (pintype "tri_state"))
      (node (ref "R28") (pin "2") (pinfunction "2_2") (pintype "passive"))
    )
    (net (code "60") (name "Net-(IC5A-QH*)") (class "Default")
      (node (ref "IC5") (pin "9") (pinfunction "QH*_9") (pintype "tri_state"))
      (node (ref "IC7") (pin "14") (pinfunction "SER_14") (pintype "input"))
    )
    (net (code "61") (name "Net-(IC6-AREF)") (class "Default")
      (node (ref "C10") (pin "1") (pinfunction "1_1") (pintype "passive"))
      (node (ref "IC6") (pin "21") (pinfunction "AREF_21") (pintype "passive"))
    )
    (net (code "62") (name "Net-(IC6-AVCC)") (class "Default")
      (node (ref "C12") (pin "1") (pinfunction "1_1") (pintype "passive"))
      (node (ref "IC6") (pin "20") (pinfunction "AVCC_20") (pintype "passive"))
      (node (ref "L1") (pin "2") (pinfunction "2_2") (pintype "passive"))
    )
    (net (code "63") (name "Net-(IC6-PB1(OC1A{slash}PCINT1))") (class "Default")
      (node (ref "IC6") (pin "15") (pinfunction "PB1(OC1A/PCINT1)_15") (pintype "bidirectional"))
      (node (ref "SA1") (pin "1$O") (pinfunction "O_1$O") (pintype "passive"))
    )
    (net (code "64") (name "Net-(IC6-PB4(MISO{slash}PCINT4))") (class "Default")
      (node (ref "IC6") (pin "18") (pinfunction "PB4(MISO/PCINT4)_18") (pintype "bidirectional"))
      (node (ref "JP1") (pin "2") (pinfunction "2_2") (pintype "passive"))
    )
    (net (code "65") (name "Net-(IC6-PB6(XTAL1{slash}TOSC1{slash}PCINT6))") (class "Default")
      (node (ref "C7") (pin "2") (pinfunction "2_2") (pintype "passive"))
      (node (ref "IC6") (pin "9") (pinfunction "PB6(XTAL1/TOSC1/PCINT6)_9") (pintype "bidirectional"))
      (node (ref "Q1") (pin "2") (pinfunction "2_2") (pintype "passive"))
    )
    (net (code "66") (name "Net-(IC6-PB7(XTAL2{slash}TOSC2{slash}PCINT7))") (class "Default")
      (node (ref "C9") (pin "2") (pinfunction "2_2") (pintype "passive"))
      (node (ref "IC6") (pin "10") (pinfunction "PB7(XTAL2/TOSC2/PCINT7)_10") (pintype "bidirectional"))
      (node (ref "Q1") (pin "1") (pinfunction "1_1") (pintype "passive"))
    )
    (net (code "67") (name "Net-(IC6-PC0(ADC0{slash}PCINT8))") (class "Default")
      (node (ref "IC6") (pin "23") (pinfunction "PC0(ADC0/PCINT8)_23") (pintype "bidirectional"))
      (node (ref "R48") (pin "2") (pinfunction "3_2") (pintype "passive"))
    )
    (net (code "68") (name "Net-(IC6-PC6({slash}RESET{slash}PCINT14))") (class "Default")
      (node (ref "IC6") (pin "1") (pinfunction "PC6(/RESET/PCINT14)_1") (pintype "bidirectional"))
      (node (ref "JP1") (pin "4") (pinfunction "4_4") (pintype "passive"))
      (node (ref "R47") (pin "2") (pinfunction "2_2") (pintype "passive"))
    )
    (net (code "69") (name "Net-(IC6-PD1(TXD{slash}PCINT17))") (class "Default")
      (node (ref "C13") (pin "1") (pinfunction "1_1") (pintype "passive"))
      (node (ref "IC6") (pin "3") (pinfunction "PD1(TXD/PCINT17)_3") (pintype "bidirectional"))
      (node (ref "SA1") (pin "1$S") (pinfunction "S_1$S") (pintype "passive"))
      (node (ref "SA2") (pin "1$P") (pinfunction "P_1$P") (pintype "passive"))
    )
    (net (code "70") (name "Net-(IC6-PD2(INT0{slash}PCINT18))") (class "Default")
      (node (ref "C14") (pin "1") (pinfunction "1_1") (pintype "passive"))
      (node (ref "IC6") (pin "4") (pinfunction "PD2(INT0/PCINT18)_4") (pintype "bidirectional"))
      (node (ref "R52") (pin "2") (pinfunction "2_2") (pintype "passive"))
      (node (ref "SA6") (pin "P$1") (pinfunction "1_P$1") (pintype "passive"))
      (node (ref "SA6") (pin "P$2") (pinfunction "1_P$2") (pintype "passive"))
    )
    (net (code "71") (name "Net-(IC7A-QA)") (class "Default")
      (node (ref "IC7") (pin "15") (pinfunction "QA_15") (pintype "tri_state"))
      (node (ref "R29") (pin "2") (pinfunction "2_2") (pintype "passive"))
    )
    (net (code "72") (name "Net-(IC7A-QB)") (class "Default")
      (node (ref "IC7") (pin "1") (pinfunction "QB_1") (pintype "tri_state"))
      (node (ref "R30") (pin "1") (pinfunction "1_1") (pintype "passive"))
    )
    (net (code "73") (name "Net-(IC7A-QG)") (class "Default")
      (node (ref "IC7") (pin "6") (pinfunction "QG_6") (pintype "tri_state"))
      (node (ref "R50") (pin "2") (pinfunction "2_2") (pintype "passive"))
    )
    (net (code "74") (name "Net-(IC7A-QH)") (class "Default")
      (node (ref "IC7") (pin "7") (pinfunction "QH_7") (pintype "tri_state"))
      (node (ref "R51") (pin "1") (pinfunction "1_1") (pintype "passive"))
    )
    (net (code "75") (name "Net-(LED1-PadA)") (class "Default")
      (node (ref "LED1") (pin "A") (pinfunction "A_A") (pintype "passive"))
      (node (ref "R5") (pin "1") (pinfunction "1_1") (pintype "passive"))
    )
    (net (code "76") (name "Net-(LED2-PadA)") (class "Default")
      (node (ref "LED2") (pin "A") (pinfunction "A_A") (pintype "passive"))
      (node (ref "R12") (pin "1") (pinfunction "1_1") (pintype "passive"))
    )
    (net (code "77") (name "Net-(LED3-PadA)") (class "Default")
      (node (ref "LED3") (pin "A") (pinfunction "A_A") (pintype "passive"))
      (node (ref "R50") (pin "1") (pinfunction "1_1") (pintype "passive"))
    )
    (net (code "78") (name "Net-(LED4-PadA)") (class "Default")
      (node (ref "LED4") (pin "A") (pinfunction "A_A") (pintype "passive"))
      (node (ref "R51") (pin "2") (pinfunction "2_2") (pintype "passive"))
    )
    (net (code "79") (name "Net-(R7-E)") (class "Default")
      (node (ref "R4") (pin "1") (pinfunction "1_1") (pintype "passive"))
      (node (ref "R7") (pin "3") (pinfunction "E_3") (pintype "passive"))
    )
    (net (code "80") (name "Net-(R15-E)") (class "Default")
      (node (ref "R11") (pin "1") (pinfunction "1_1") (pintype "passive"))
      (node (ref "R15") (pin "3") (pinfunction "E_3") (pintype "passive"))
    )
    (net (code "81") (name "Net-(R16B-2)") (class "Default")
      (node (ref "R16") (pin "4") (pinfunction "2_4") (pintype "passive"))
      (node (ref "SA4") (pin "1$P") (pinfunction "P_1$P") (pintype "passive"))
    )
    (net (code "82") (name "Net-(R48-Pad1)") (class "Default")
      (node (ref "R48") (pin "1") (pinfunction "1_1") (pintype "passive"))
      (node (ref "R53") (pin "2") (pinfunction "2_2") (pintype "passive"))
    )
    (net (code "83") (name "Net-(R54-Pad2)") (class "Default")
      (node (ref "R54") (pin "2") (pinfunction "2_2") (pintype "passive"))
      (node (ref "R8") (pin "1") (pinfunction "1_1") (pintype "passive"))
      (node (ref "VT6") (pin "G") (pinfunction "G_G") (pintype "passive"))
    )
    (net (code "84") (name "Net-(R55-Pad2)") (class "Default")
      (node (ref "R55") (pin "2") (pinfunction "2_2") (pintype "passive"))
      (node (ref "R6") (pin "2") (pinfunction "2_2") (pintype "passive"))
      (node (ref "VT7") (pin "G") (pinfunction "G_G") (pintype "passive"))
    )
    (net (code "85") (name "Net-(SA1-P)") (class "Default")
      (node (ref "R14") (pin "1") (pinfunction "1_1") (pintype "passive"))
      (node (ref "R3") (pin "2") (pinfunction "2_2") (pintype "passive"))
      (node (ref "SA1") (pin "1$P") (pinfunction "P_1$P") (pintype "passive"))
    )
    (net (code "86") (name "Net-(SA2-O)") (class "Default")
      (node (ref "R49") (pin "1") (pinfunction "1_1") (pintype "passive"))
      (node (ref "SA2") (pin "1$O") (pinfunction "O_1$O") (pintype "passive"))
    )
    (net (code "87") (name "Net-(SA3-P)") (class "Default")
      (node (ref "R16") (pin "2") (pinfunction "2_2") (pintype "passive"))
      (node (ref "SA3") (pin "1$P") (pinfunction "P_1$P") (pintype "passive"))
    )
    (net (code "88") (name "Net-(SA3-S)") (class "Default")
      (node (ref "SA3") (pin "1$S") (pinfunction "S_1$S") (pintype "passive"))
      (node (ref "SA4") (pin "1$S") (pinfunction "S_1$S") (pintype "passive"))
      (node (ref "XS2") (pin "1") (pinfunction "1_1") (pintype "passive"))
    )
    (net (code "89") (name "Net-(SA5-P)") (class "Default")
      (node (ref "F1") (pin "2") (pinfunction "2_2") (pintype "passive"))
      (node (ref "SA5") (pin "2") (pinfunction "P_2") (pintype "passive"))
    )
    (net (code "90") (name "Net-(SA5-S)") (class "Default")
      (node (ref "C5") (pin "1") (pinfunction "1_1") (pintype "passive"))
      (node (ref "R1") (pin "2") (pinfunction "2_2") (pintype "passive"))
      (node (ref "R13") (pin "2") (pinfunction "2_2") (pintype "passive"))
      (node (ref "R2") (pin "2") (pinfunction "2_2") (pintype "passive"))
      (node (ref "SA5") (pin "3") (pinfunction "S_3") (pintype "passive"))
      (node (ref "U$3") (pin "1") (pinfunction "IN_1") (pintype "input"))
      (node (ref "VT1") (pin "S") (pinfunction "S_S") (pintype "passive"))
      (node (ref "VT5") (pin "S") (pinfunction "S_S") (pintype "passive"))
    )
    (net (code "91") (name "Net-(VT2-B)") (class "Default")
      (node (ref "R2") (pin "1") (pinfunction "1_1") (pintype "passive"))
      (node (ref "VT2") (pin "2") (pinfunction "B_2") (pintype "passive"))
      (node (ref "VT3") (pin "1") (pinfunction "C_1") (pintype "passive"))
    )
    (net (code "92") (name "Net-(VT2-C)") (class "Default")
      (node (ref "R1") (pin "1") (pinfunction "1_1") (pintype "passive"))
      (node (ref "VT1") (pin "G") (pinfunction "G_G") (pintype "passive"))
      (node (ref "VT2") (pin "1") (pinfunction "C_1") (pintype "passive"))
    )
    (net (code "93") (name "Net-(VT3-B)") (class "Default")
      (node (ref "R3") (pin "1") (pinfunction "1_1") (pintype "passive"))
      (node (ref "VT3") (pin "2") (pinfunction "B_2") (pintype "passive"))
    )
    (net (code "94") (name "Net-(VT4-B)") (class "Default")
      (node (ref "R14") (pin "2") (pinfunction "2_2") (pintype "passive"))
      (node (ref "VT4") (pin "2") (pinfunction "B_2") (pintype "passive"))
    )
    (net (code "95") (name "Net-(VT4-C)") (class "Default")
      (node (ref "R13") (pin "1") (pinfunction "1_1") (pintype "passive"))
      (node (ref "VT4") (pin "1") (pinfunction "C_1") (pintype "passive"))
      (node (ref "VT5") (pin "G") (pinfunction "G_G") (pintype "passive"))
    )
    (net (code "96") (name "Net-(VT8-B)") (class "Default")
      (node (ref "R41") (pin "2") (pinfunction "2_2") (pintype "passive"))
      (node (ref "R43") (pin "1") (pinfunction "1_1") (pintype "passive"))
      (node (ref "VT8") (pin "2") (pinfunction "B_2") (pintype "passive"))
    )
    (net (code "97") (name "Net-(VT8-C)") (class "Default")
      (node (ref "HG1") (pin "A1") (pinfunction "A1_A1") (pintype "input"))
      (node (ref "VT8") (pin "1") (pinfunction "C_1") (pintype "passive"))
    )
    (net (code "98") (name "Net-(VT9-B)") (class "Default")
      (node (ref "R40") (pin "2") (pinfunction "2_2") (pintype "passive"))
      (node (ref "R44") (pin "1") (pinfunction "1_1") (pintype "passive"))
      (node (ref "VT9") (pin "2") (pinfunction "B_2") (pintype "passive"))
    )
    (net (code "99") (name "Net-(VT9-C)") (class "Default")
      (node (ref "HG1") (pin "A2") (pinfunction "A2_A2") (pintype "input"))
      (node (ref "VT9") (pin "1") (pinfunction "C_1") (pintype "passive"))
    )
    (net (code "100") (name "Net-(VT10-B)") (class "Default")
      (node (ref "R39") (pin "2") (pinfunction "2_2") (pintype "passive"))
      (node (ref "R45") (pin "1") (pinfunction "1_1") (pintype "passive"))
      (node (ref "VT10") (pin "2") (pinfunction "B_2") (pintype "passive"))
    )
    (net (code "101") (name "Net-(VT10-C)") (class "Default")
      (node (ref "HG1") (pin "A3") (pinfunction "A3_A3") (pintype "input"))
      (node (ref "VT10") (pin "1") (pinfunction "C_1") (pintype "passive"))
    )
    (net (code "102") (name "Net-(VT11-B)") (class "Default")
      (node (ref "R42") (pin "2") (pinfunction "2_2") (pintype "passive"))
      (node (ref "R46") (pin "1") (pinfunction "1_1") (pintype "passive"))
      (node (ref "VT11") (pin "2") (pinfunction "B_2") (pintype "passive"))
    )
    (net (code "103") (name "Net-(VT11-C)") (class "Default")
      (node (ref "HG1") (pin "A4") (pinfunction "A4_A4") (pintype "input"))
      (node (ref "VT11") (pin "1") (pinfunction "C_1") (pintype "passive"))
    )
    (net (code "104") (name "VCC") (class "Default")
      (node (ref "C11") (pin "+") (pinfunction "+_+") (pintype "passive"))
      (node (ref "C6") (pin "+") (pinfunction "+_+") (pintype "passive"))
      (node (ref "C8") (pin "1") (pinfunction "1_1") (pintype "passive"))
      (node (ref "IC3") (pin "10") (pinfunction "SCL_10") (pintype "input"))
      (node (ref "IC4") (pin "10") (pinfunction "SCL_10") (pintype "input"))
      (node (ref "IC5") (pin "10") (pinfunction "SCL_10") (pintype "input"))
      (node (ref "IC6") (pin "7") (pinfunction "VCC_7") (pintype "power_in"))
      (node (ref "IC7") (pin "10") (pinfunction "SCL_10") (pintype "input"))
      (node (ref "JP1") (pin "5") (pinfunction "5_5") (pintype "passive"))
      (node (ref "L1") (pin "1") (pinfunction "1_1") (pintype "passive"))
      (node (ref "R43") (pin "2") (pinfunction "2_2") (pintype "passive"))
      (node (ref "R44") (pin "2") (pinfunction "2_2") (pintype "passive"))
      (node (ref "R45") (pin "2") (pinfunction "2_2") (pintype "passive"))
      (node (ref "R46") (pin "2") (pinfunction "2_2") (pintype "passive"))
      (node (ref "R47") (pin "1") (pinfunction "1_1") (pintype "passive"))
      (node (ref "R48") (pin "3") (pinfunction "2_3") (pintype "passive"))
      (node (ref "R49") (pin "2") (pinfunction "2_2") (pintype "passive"))
      (node (ref "R52") (pin "1") (pinfunction "1_1") (pintype "passive"))
      (node (ref "U$3") (pin "3") (pinfunction "OUT_3") (pintype "passive"))
      (node (ref "VT10") (pin "3") (pinfunction "E_3") (pintype "passive"))
      (node (ref "VT11") (pin "3") (pinfunction "E_3") (pintype "passive"))
      (node (ref "VT8") (pin "3") (pinfunction "E_3") (pintype "passive"))
      (node (ref "VT9") (pin "3") (pinfunction "E_3") (pintype "passive"))
    )
    (net (code "105") (name "unconnected-(IC4A-QE-Pad4)") (class "Default")
      (node (ref "IC4") (pin "4") (pinfunction "QE_4") (pintype "tri_state"))
    )
    (net (code "106") (name "unconnected-(IC4A-QF-Pad5)") (class "Default")
      (node (ref "IC4") (pin "5") (pinfunction "QF_5") (pintype "tri_state"))
    )
    (net (code "107") (name "unconnected-(IC4A-QG-Pad6)") (class "Default")
      (node (ref "IC4") (pin "6") (pinfunction "QG_6") (pintype "tri_state"))
    )
    (net (code "108") (name "unconnected-(IC4A-QH-Pad7)") (class "Default")
      (node (ref "IC4") (pin "7") (pinfunction "QH_7") (pintype "tri_state"))
    )
    (net (code "109") (name "unconnected-(IC6-PB0(ICP1{slash}CLKO{slash}PCINT0)-Pad14)") (class "Default")
      (node (ref "IC6") (pin "14") (pinfunction "PB0(ICP1/CLKO/PCINT0)_14") (pintype "bidirectional"))
    )
    (net (code "110") (name "unconnected-(IC6-PC1(ADC1{slash}PCINT9)-Pad24)") (class "Default")
      (node (ref "IC6") (pin "24") (pinfunction "PC1(ADC1/PCINT9)_24") (pintype "bidirectional"))
    )
    (net (code "111") (name "unconnected-(IC6-PC2(ADC2{slash}PCINT10)-Pad25)") (class "Default")
      (node (ref "IC6") (pin "25") (pinfunction "PC2(ADC2/PCINT10)_25") (pintype "bidirectional"))
    )
    (net (code "112") (name "unconnected-(IC6-PC3(ADC3{slash}PCINT11)-Pad26)") (class "Default")
      (node (ref "IC6") (pin "26") (pinfunction "PC3(ADC3/PCINT11)_26") (pintype "bidirectional"))
    )
    (net (code "113") (name "unconnected-(IC6-PD0(RXD{slash}PCINT16)-Pad2)") (class "Default")
      (node (ref "IC6") (pin "2") (pinfunction "PD0(RXD/PCINT16)_2") (pintype "bidirectional"))
    )
    (net (code "114") (name "unconnected-(IC6-PD3(INT1{slash}OC2B{slash}PCINT19)-Pad5)") (class "Default")
      (node (ref "IC6") (pin "5") (pinfunction "PD3(INT1/OC2B/PCINT19)_5") (pintype "bidirectional"))
    )
    (net (code "115") (name "unconnected-(IC6-PD4(T0{slash}XCK{slash}PCINT20)-Pad6)") (class "Default")
      (node (ref "IC6") (pin "6") (pinfunction "PD4(T0/XCK/PCINT20)_6") (pintype "bidirectional"))
    )
    (net (code "116") (name "unconnected-(IC6-PD5(T1{slash}OC0B{slash}PCINT21)-Pad11)") (class "Default")
      (node (ref "IC6") (pin "11") (pinfunction "PD5(T1/OC0B/PCINT21)_11") (pintype "bidirectional"))
    )
    (net (code "117") (name "unconnected-(IC6-PD6(AIN0{slash}OC0A{slash}PCINT22)-Pad12)") (class "Default")
      (node (ref "IC6") (pin "12") (pinfunction "PD6(AIN0/OC0A/PCINT22)_12") (pintype "bidirectional"))
    )
    (net (code "118") (name "unconnected-(IC6-PD7(AIN1{slash}PCINT23)-Pad13)") (class "Default")
      (node (ref "IC6") (pin "13") (pinfunction "PD7(AIN1/PCINT23)_13") (pintype "bidirectional"))
    )
    (net (code "119") (name "unconnected-(IC7A-QC-Pad2)") (class "Default")
      (node (ref "IC7") (pin "2") (pinfunction "QC_2") (pintype "tri_state"))
    )
    (net (code "120") (name "unconnected-(IC7A-QD-Pad3)") (class "Default")
      (node (ref "IC7") (pin "3") (pinfunction "QD_3") (pintype "tri_state"))
    )
    (net (code "121") (name "unconnected-(IC7A-QE-Pad4)") (class "Default")
      (node (ref "IC7") (pin "4") (pinfunction "QE_4") (pintype "tri_state"))
    )
    (net (code "122") (name "unconnected-(IC7A-QF-Pad5)") (class "Default")
      (node (ref "IC7") (pin "5") (pinfunction "QF_5") (pintype "tri_state"))
    )
    (net (code "123") (name "unconnected-(IC7A-QH*-Pad9)") (class "Default")
      (node (ref "IC7") (pin "9") (pinfunction "QH*_9") (pintype "tri_state"))
    )
    (net (code "124") (name "unconnected-(J1-Pad2)") (class "Default")
      (node (ref "J1") (pin "2") (pinfunction "2_2") (pintype "passive"))
    )
    (net (code "125") (name "unconnected-(SA3-O-Pad1$O)") (class "Default")
      (node (ref "SA3") (pin "1$O") (pinfunction "O_1$O") (pintype "passive"))
    )
    (net (code "126") (name "unconnected-(SA4-O-Pad1$O)") (class "Default")
      (node (ref "SA4") (pin "1$O") (pinfunction "O_1$O") (pintype "passive"))
    )
    (net (code "127") (name "unconnected-(SA5-O-Pad1)") (class "Default")
      (node (ref "SA5") (pin "1") (pinfunction "O_1") (pintype "passive"))
    )
  )
)
